# working.net
KiCad netlist of a schematic drawn in EAGLE
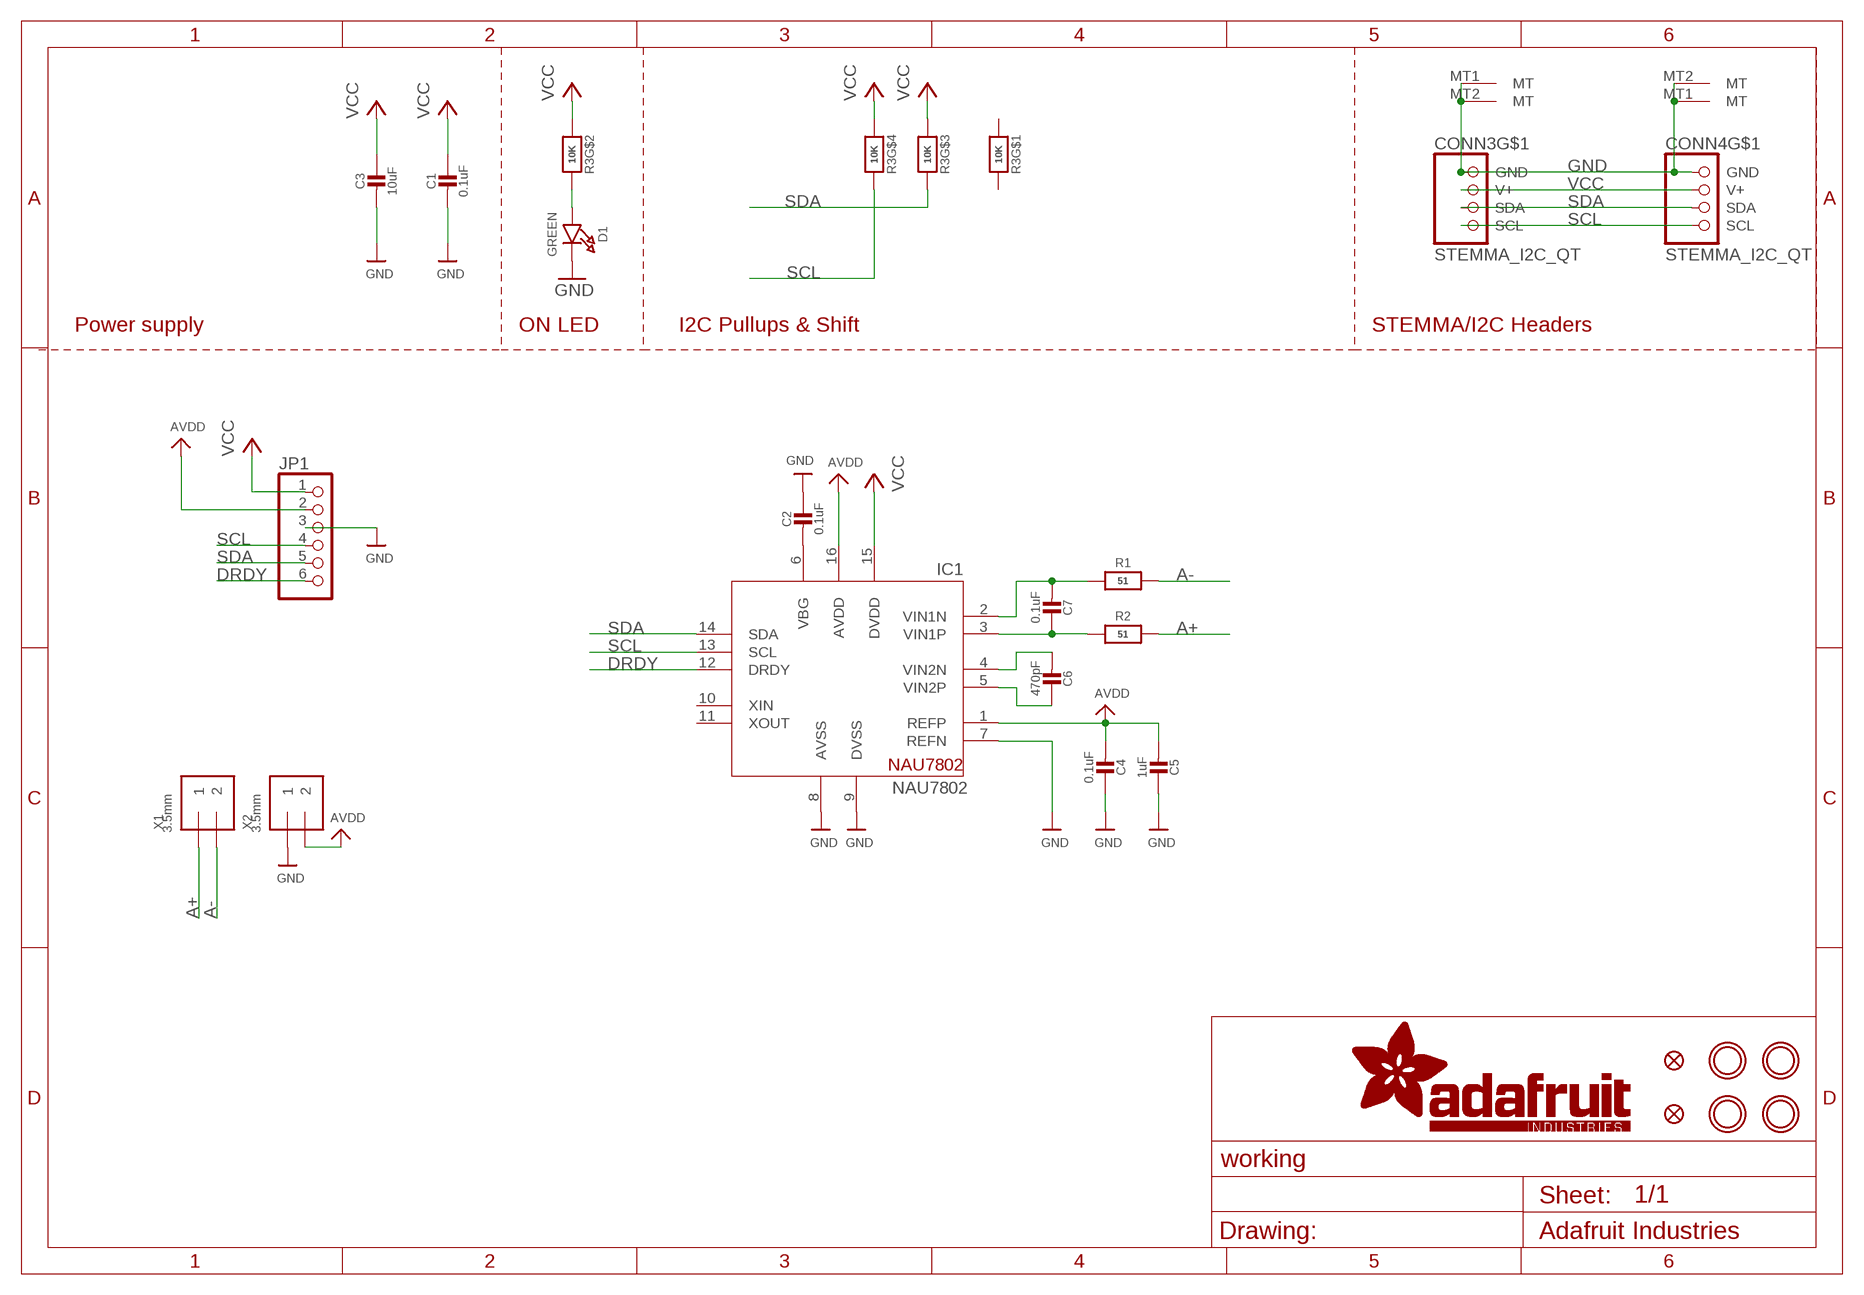
[diagram p0: schematic, sheet 1]

(export (version "E")
  (design (tool "Eeschema 10.0.6"))
  (components
    (comp (ref "C1")
      (value "0.1uF")
      (footprint "eagle-import:0603-NO")
      (libsource (lib "eagle-import") (part "CAP_CERAMIC0603_NO"))
    )
    (comp (ref "C2")
      (value "0.1uF")
      (footprint "eagle-import:0603-NO")
      (libsource (lib "eagle-import") (part "CAP_CERAMIC0603_NO"))
    )
    (comp (ref "C3")
      (value "10uF")
      (footprint "eagle-import:0805-NO")
      (libsource (lib "eagle-import") (part "CAP_CERAMIC0805-NOOUTLINE"))
    )
    (comp (ref "C4")
      (value "0.1uF")
      (footprint "eagle-import:0603-NO")
      (libsource (lib "eagle-import") (part "CAP_CERAMIC0603_NO"))
    )
    (comp (ref "C5")
      (value "1uF")
      (footprint "eagle-import:0603-NO")
      (libsource (lib "eagle-import") (part "CAP_CERAMIC0603_NO"))
    )
    (comp (ref "C6")
      (value "470pF")
      (footprint "eagle-import:0603-NO")
      (libsource (lib "eagle-import") (part "CAP_CERAMIC0603_NO"))
    )
    (comp (ref "C7")
      (value "0.1uF")
      (footprint "eagle-import:0603-NO")
      (libsource (lib "eagle-import") (part "CAP_CERAMIC0603_NO"))
    )
    (comp (ref "CONN3")
      (value "STEMMA_I2C_QT")
      (footprint "eagle-import:JST_SH4")
      (libsource (lib "eagle-import") (part "STEMMA_I2C_QT"))
    )
    (comp (ref "CONN4")
      (value "STEMMA_I2C_QT")
      (footprint "eagle-import:JST_SH4")
      (libsource (lib "eagle-import") (part "STEMMA_I2C_QT"))
    )
    (comp (ref "D1")
      (value "GREEN")
      (footprint "eagle-import:CHIPLED_0603_NOOUTLINE")
      (libsource (lib "eagle-import") (part "LED0603_NOOUTLINE"))
    )
    (comp (ref "FID3")
      (value "FIDUCIAL_1MM")
      (footprint "eagle-import:FIDUCIAL_1MM")
      (libsource (lib "eagle-import") (part "FIDUCIAL_1MM"))
    )
    (comp (ref "FID4")
      (value "FIDUCIAL_1MM")
      (footprint "eagle-import:FIDUCIAL_1MM")
      (libsource (lib "eagle-import") (part "FIDUCIAL_1MM"))
    )
    (comp (ref "IC1")
      (value "NAU7802")
      (footprint "eagle-import:SOIC16_NARROW")
      (libsource (lib "eagle-import") (part "NAU7802"))
    )
    (comp (ref "JP1")
      (value "HEADER-1X670MIL")
      (footprint "eagle-import:1X06_ROUND_70")
      (libsource (lib "eagle-import") (part "HEADER-1X670MIL"))
    )
    (comp (ref "R1")
      (value "51")
      (footprint "eagle-import:0603-NO")
      (libsource (lib "eagle-import") (part "RESISTOR_0603_NOOUT"))
    )
    (comp (ref "R2")
      (value "51")
      (footprint "eagle-import:0603-NO")
      (libsource (lib "eagle-import") (part "RESISTOR_0603_NOOUT"))
    )
    (comp (ref "R3")
      (value "10K")
      (footprint "eagle-import:RESPACK_4X0603")
      (libsource (lib "eagle-import") (part "RESISTOR_4PACK"))
    )
    (comp (ref "U$1")
      (value "MOUNTINGHOLE2.5")
      (footprint "eagle-import:MOUNTINGHOLE_2.5_PLATED")
      (libsource (lib "eagle-import") (part "MOUNTINGHOLE2.5"))
    )
    (comp (ref "U$17")
      (value "MOUNTINGHOLE2.5")
      (footprint "eagle-import:MOUNTINGHOLE_2.5_PLATED")
      (libsource (lib "eagle-import") (part "MOUNTINGHOLE2.5"))
    )
    (comp (ref "U$19")
      (value "MOUNTINGHOLE2.5")
      (footprint "eagle-import:MOUNTINGHOLE_2.5_PLATED")
      (libsource (lib "eagle-import") (part "MOUNTINGHOLE2.5"))
    )
    (comp (ref "U$21")
      (value "MOUNTINGHOLE2.5")
      (footprint "eagle-import:MOUNTINGHOLE_2.5_PLATED")
      (libsource (lib "eagle-import") (part "MOUNTINGHOLE2.5"))
    )
    (comp (ref "X1")
      (value "3.5mm")
      (footprint "eagle-import:TERMBLOCK_1X2-3.5MM")
      (libsource (lib "eagle-import") (part "TERMBLOCK_1X2_3.5MM"))
    )
    (comp (ref "X2")
      (value "3.5mm")
      (footprint "eagle-import:TERMBLOCK_1X2-3.5MM")
      (libsource (lib "eagle-import") (part "TERMBLOCK_1X2_3.5MM"))
    )
  )
  (nets
    (net (code "1") (name "/A+") (class "Default")
      (node (ref "R2") (pin "2") (pinfunction "2_2") (pintype "passive"))
      (node (ref "X1") (pin "1") (pinfunction "1_1") (pintype "passive"))
    )
    (net (code "2") (name "/A-") (class "Default")
      (node (ref "R1") (pin "2") (pinfunction "2_2") (pintype "passive"))
      (node (ref "X1") (pin "2") (pinfunction "2_2") (pintype "passive"))
    )
    (net (code "3") (name "/DRDY") (class "Default")
      (node (ref "IC1") (pin "12") (pinfunction "DRDY_12") (pintype "output"))
      (node (ref "JP1") (pin "6") (pinfunction "6_6") (pintype "passive"))
    )
    (net (code "4") (name "/SCL") (class "Default")
      (node (ref "CONN3") (pin "4") (pinfunction "SCL_4") (pintype "passive"))
      (node (ref "CONN4") (pin "4") (pinfunction "SCL_4") (pintype "passive"))
      (node (ref "IC1") (pin "13") (pinfunction "SCL_13") (pintype "bidirectional"))
      (node (ref "JP1") (pin "4") (pinfunction "4_4") (pintype "passive"))
      (node (ref "R3") (pin "5") (pinfunction "2_5") (pintype "passive"))
    )
    (net (code "5") (name "/SDA") (class "Default")
      (node (ref "CONN3") (pin "3") (pinfunction "SDA_3") (pintype "passive"))
      (node (ref "CONN4") (pin "3") (pinfunction "SDA_3") (pintype "passive"))
      (node (ref "IC1") (pin "14") (pinfunction "SDA_14") (pintype "bidirectional"))
      (node (ref "JP1") (pin "5") (pinfunction "5_5") (pintype "passive"))
      (node (ref "R3") (pin "6") (pinfunction "2_6") (pintype "passive"))
    )
    (net (code "6") (name "AVDD") (class "Default")
      (node (ref "C4") (pin "2") (pinfunction "2_2") (pintype "passive"))
      (node (ref "C5") (pin "2") (pinfunction "2_2") (pintype "passive"))
      (node (ref "IC1") (pin "1") (pinfunction "REFP_1") (pintype "input"))
      (node (ref "IC1") (pin "16") (pinfunction "AVDD_16") (pintype "power_in"))
      (node (ref "JP1") (pin "2") (pinfunction "2_2") (pintype "passive"))
      (node (ref "X2") (pin "2") (pinfunction "2_2") (pintype "passive"))
    )
    (net (code "7") (name "GND") (class "Default")
      (node (ref "C1") (pin "2") (pinfunction "2_2") (pintype "passive"))
      (node (ref "C2") (pin "1") (pinfunction "1_1") (pintype "passive"))
      (node (ref "C3") (pin "2") (pinfunction "2_2") (pintype "passive"))
      (node (ref "C4") (pin "1") (pinfunction "1_1") (pintype "passive"))
      (node (ref "C5") (pin "1") (pinfunction "1_1") (pintype "passive"))
      (node (ref "CONN3") (pin "1") (pinfunction "GND_1") (pintype "passive"))
      (node (ref "CONN3") (pin "MT1") (pinfunction "MT_MT1") (pintype "bidirectional"))
      (node (ref "CONN3") (pin "MT2") (pinfunction "MT_MT2") (pintype "bidirectional"))
      (node (ref "CONN4") (pin "1") (pinfunction "GND_1") (pintype "passive"))
      (node (ref "CONN4") (pin "MT1") (pinfunction "MT_MT1") (pintype "bidirectional"))
      (node (ref "CONN4") (pin "MT2") (pinfunction "MT_MT2") (pintype "bidirectional"))
      (node (ref "D1") (pin "C") (pinfunction "C_C") (pintype "passive"))
      (node (ref "IC1") (pin "7") (pinfunction "REFN_7") (pintype "input"))
      (node (ref "IC1") (pin "8") (pinfunction "AVSS_8") (pintype "power_in"))
      (node (ref "IC1") (pin "9") (pinfunction "DVSS_9") (pintype "power_in"))
      (node (ref "JP1") (pin "3") (pinfunction "3_3") (pintype "passive"))
      (node (ref "X2") (pin "1") (pinfunction "1_1") (pintype "passive"))
    )
    (net (code "8") (name "Net-(IC1-VBG)") (class "Default")
      (node (ref "C2") (pin "2") (pinfunction "2_2") (pintype "passive"))
      (node (ref "IC1") (pin "6") (pinfunction "VBG_6") (pintype "power_in"))
    )
    (net (code "9") (name "Net-(IC1-VIN1N)") (class "Default")
      (node (ref "C7") (pin "2") (pinfunction "2_2") (pintype "passive"))
      (node (ref "IC1") (pin "2") (pinfunction "VIN1N_2") (pintype "input"))
      (node (ref "R1") (pin "1") (pinfunction "1_1") (pintype "passive"))
    )
    (net (code "10") (name "Net-(IC1-VIN1P)") (class "Default")
      (node (ref "C7") (pin "1") (pinfunction "1_1") (pintype "passive"))
      (node (ref "IC1") (pin "3") (pinfunction "VIN1P_3") (pintype "input"))
      (node (ref "R2") (pin "1") (pinfunction "1_1") (pintype "passive"))
    )
    (net (code "11") (name "Net-(IC1-VIN2N)") (class "Default")
      (node (ref "C6") (pin "2") (pinfunction "2_2") (pintype "passive"))
      (node (ref "IC1") (pin "4") (pinfunction "VIN2N_4") (pintype "input"))
    )
    (net (code "12") (name "Net-(IC1-VIN2P)") (class "Default")
      (node (ref "C6") (pin "1") (pinfunction "1_1") (pintype "passive"))
      (node (ref "IC1") (pin "5") (pinfunction "VIN2P_5") (pintype "input"))
    )
    (net (code "13") (name "Net-(R3B-2)") (class "Default")
      (node (ref "D1") (pin "A") (pinfunction "A_A") (pintype "passive"))
      (node (ref "R3") (pin "7") (pinfunction "2_7") (pintype "passive"))
    )
    (net (code "14") (name "VCC") (class "Default")
      (node (ref "C1") (pin "1") (pinfunction "1_1") (pintype "passive"))
      (node (ref "C3") (pin "1") (pinfunction "1_1") (pintype "passive"))
      (node (ref "CONN3") (pin "2") (pinfunction "V+_2") (pintype "passive"))
      (node (ref "CONN4") (pin "2") (pinfunction "V+_2") (pintype "passive"))
      (node (ref "IC1") (pin "15") (pinfunction "DVDD_15") (pintype "power_in"))
      (node (ref "JP1") (pin "1") (pinfunction "1_1") (pintype "passive"))
      (node (ref "R3") (pin "2") (pinfunction "1_2") (pintype "passive"))
      (node (ref "R3") (pin "3") (pinfunction "1_3") (pintype "passive"))
      (node (ref "R3") (pin "4") (pinfunction "1_4") (pintype "passive"))
    )
    (net (code "15") (name "unconnected-(IC1-XIN-Pad10)") (class "Default")
      (node (ref "IC1") (pin "10") (pinfunction "XIN_10") (pintype "passive"))
    )
    (net (code "16") (name "unconnected-(IC1-XOUT-Pad11)") (class "Default")
      (node (ref "IC1") (pin "11") (pinfunction "XOUT_11") (pintype "passive"))
    )
    (net (code "17") (name "unconnected-(R3-Pad1)") (class "Default")
      (node (ref "R3") (pin "1") (pinfunction "1_1") (pintype "passive"))
    )
    (net (code "18") (name "unconnected-(R3A-2-Pad8)") (class "Default")
      (node (ref "R3") (pin "8") (pinfunction "2_8") (pintype "passive"))
    )
  )
)
